# micro.net
KiCad netlist of a schematic drawn in Altium Designer
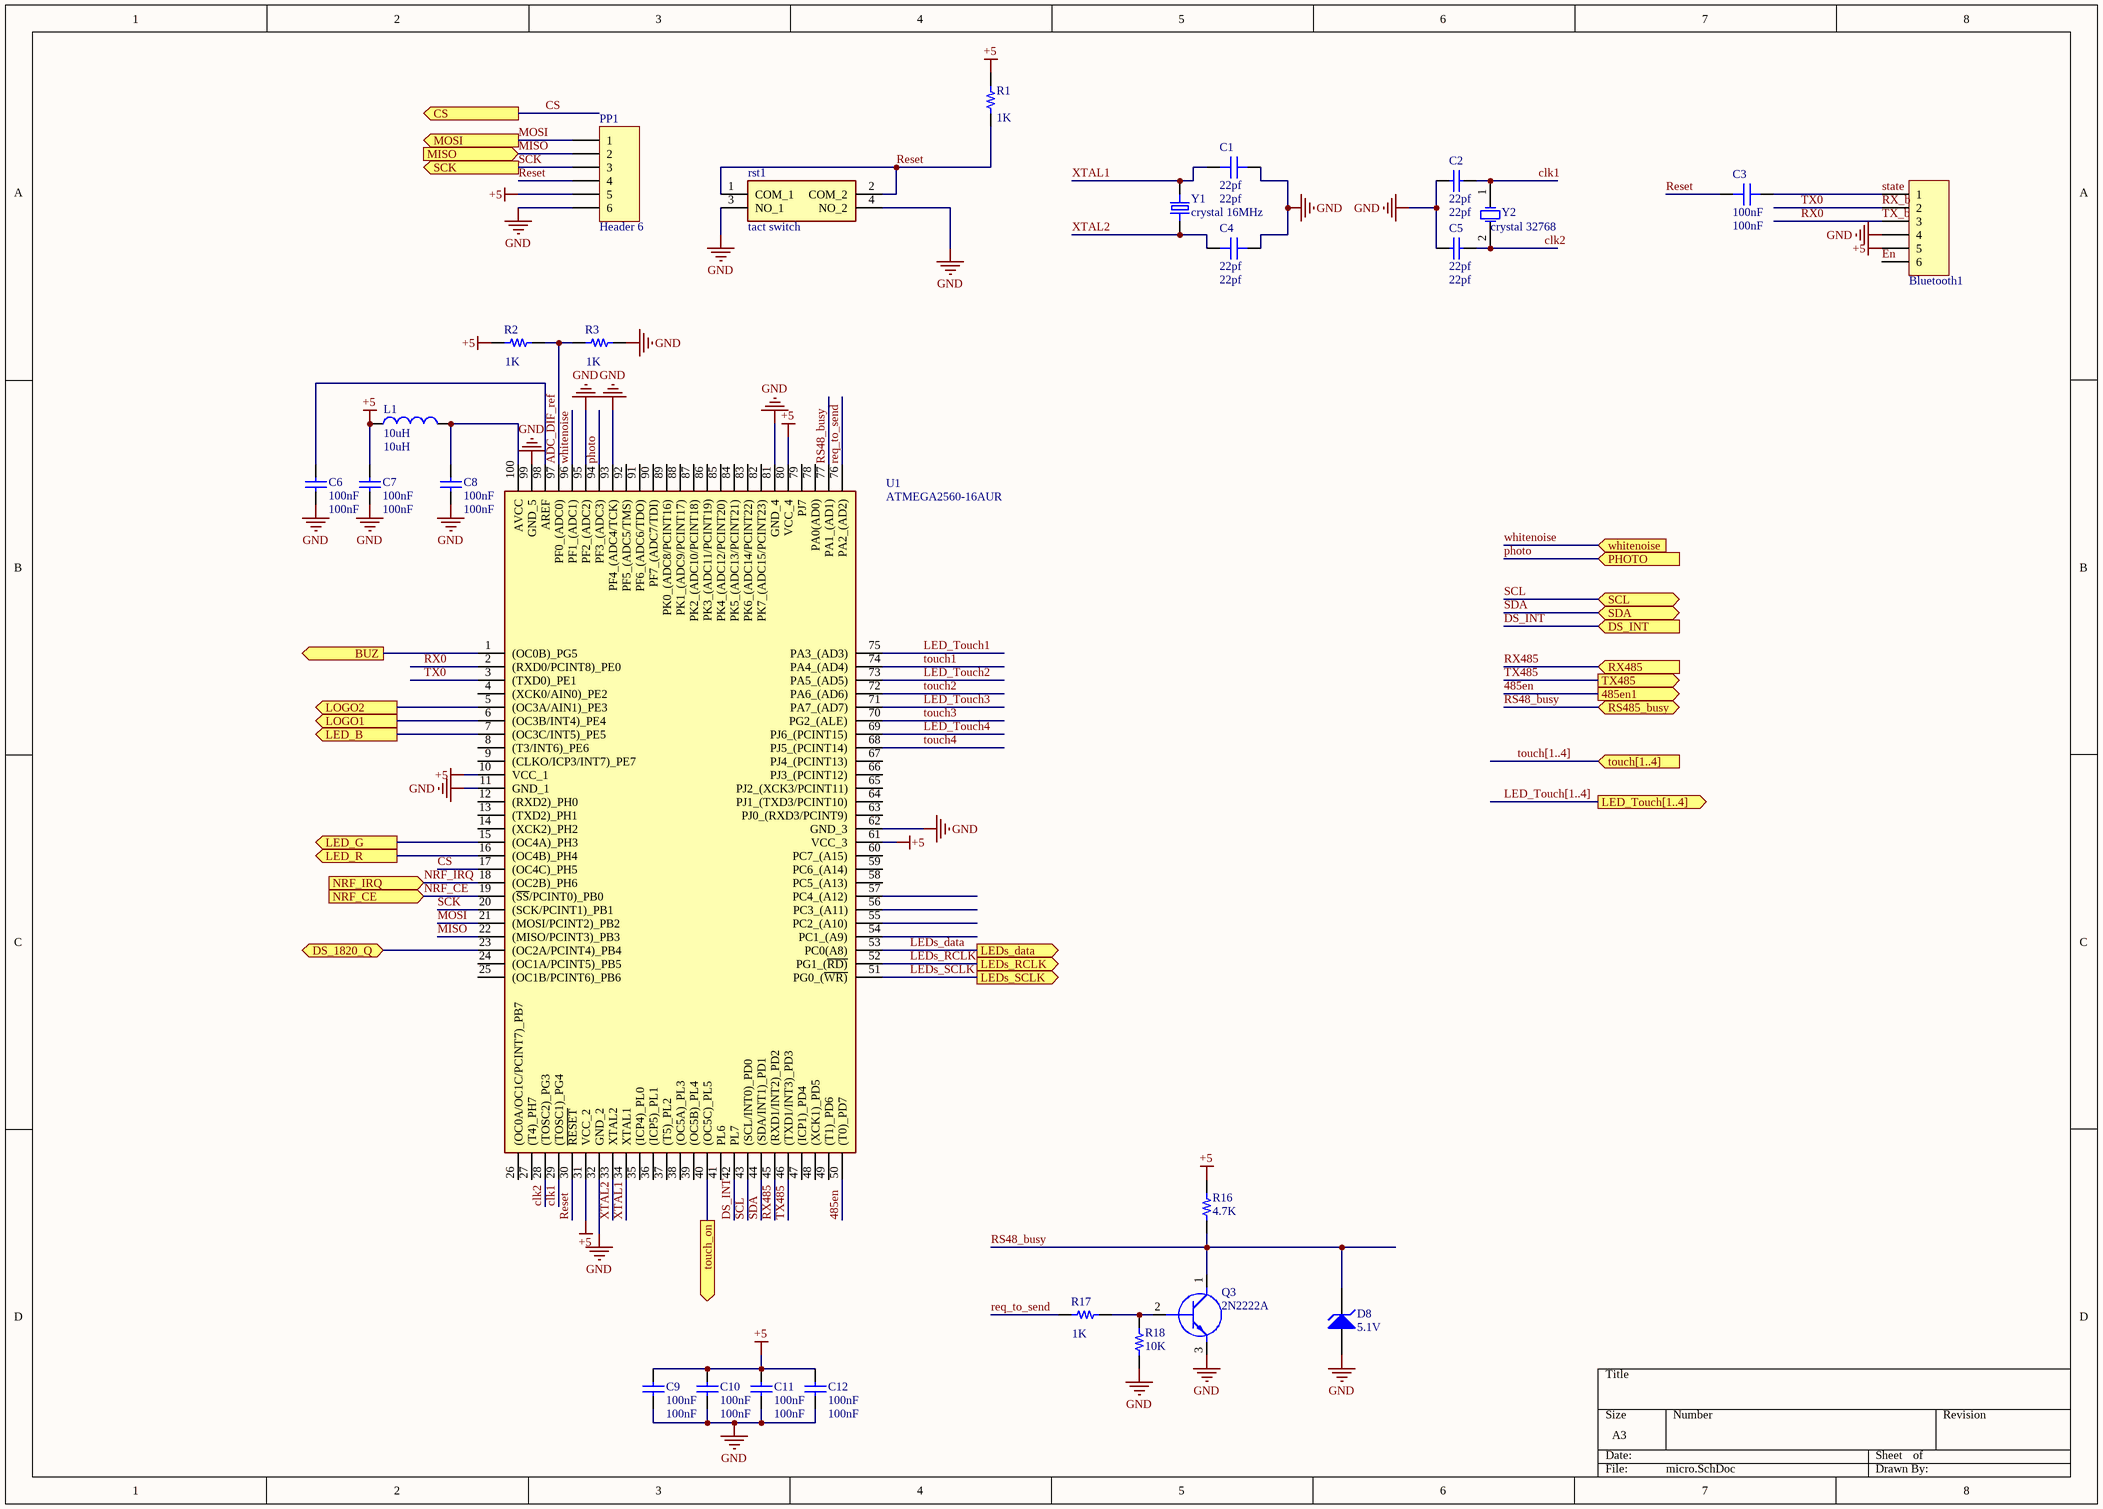
[diagram p0: micro.SchDoc]

(export (version "E")
  (design (tool "Eeschema 10.0.6"))
  (components
    (comp (ref "Bluetooth1")
      (value "Header 6")
      (footprint "H-1x6")
      (description "Header, 6-Pin , female")
      (libsource (lib "Mine-Discreet") (part "H-1x6"))
    )
    (comp (ref "C1")
      (value "22pf")
      (footprint "0603C")
      (description "CAP SMD 0603")
      (fields (field (name "PART NUMBER") "C0805X106K9RAC7800") (field (name "ALTIUM_VALUE") "22pf"))
      (libsource (lib "lamp control-ver2") (part "Capacitor"))
    )
    (comp (ref "C2")
      (value "22pf")
      (footprint "0603C")
      (description "CAP SMD 0603")
      (fields (field (name "ALTIUM_VALUE") "22pf") (field (name "PUBLISHER") "Altium Limited"))
      (libsource (lib "Miscellaneous Devices") (part "Cap"))
    )
    (comp (ref "C3")
      (value "100nF")
      (footprint "0603C")
      (description "CAP SMD 0603")
      (fields (field (name "PART NUMBER") "C0805X106K9RAC7800") (field (name "ALTIUM_VALUE") "100nF"))
      (libsource (lib "lamp control-ver2") (part "Capacitor"))
    )
    (comp (ref "C4")
      (value "22pf")
      (footprint "0603C")
      (description "CAP SMD 0603")
      (fields (field (name "PART NUMBER") "C0805X106K9RAC7800") (field (name "ALTIUM_VALUE") "22pf"))
      (libsource (lib "lamp control-ver2") (part "Capacitor"))
    )
    (comp (ref "C5")
      (value "22pf")
      (footprint "0603C")
      (description "CAP SMD 0603")
      (fields (field (name "ALTIUM_VALUE") "22pf") (field (name "PUBLISHER") "Altium Limited"))
      (libsource (lib "Miscellaneous Devices") (part "Cap"))
    )
    (comp (ref "C6")
      (value "100nF")
      (footprint "0603C")
      (description "CAP SMD 0603")
      (fields (field (name "ALTIUM_VALUE") "100nF") (field (name "PUBLISHER") "Altium Limited"))
      (libsource (lib "Miscellaneous Devices") (part "Cap"))
    )
    (comp (ref "C7")
      (value "100nF")
      (footprint "0603C")
      (description "CAP SMD 0603")
      (fields (field (name "ALTIUM_VALUE") "100nF") (field (name "PUBLISHER") "Altium Limited"))
      (libsource (lib "Miscellaneous Devices") (part "Cap"))
    )
    (comp (ref "C8")
      (value "100nF")
      (footprint "0603C")
      (description "CAP SMD 0603")
      (fields (field (name "ALTIUM_VALUE") "100nF") (field (name "PUBLISHER") "Altium Limited"))
      (libsource (lib "Miscellaneous Devices") (part "Cap"))
    )
    (comp (ref "C9")
      (value "100nF")
      (footprint "0603C")
      (description "CAP SMD 0603")
      (fields (field (name "ALTIUM_VALUE") "100nF") (field (name "PUBLISHER") "Altium Limited"))
      (libsource (lib "Miscellaneous Devices") (part "Cap"))
    )
    (comp (ref "C10")
      (value "100nF")
      (footprint "0603C")
      (description "CAP SMD 0603")
      (fields (field (name "ALTIUM_VALUE") "100nF") (field (name "PUBLISHER") "Altium Limited"))
      (libsource (lib "Miscellaneous Devices") (part "Cap"))
    )
    (comp (ref "C11")
      (value "100nF")
      (footprint "0603C")
      (description "CAP SMD 0603")
      (fields (field (name "ALTIUM_VALUE") "100nF") (field (name "PUBLISHER") "Altium Limited"))
      (libsource (lib "Miscellaneous Devices") (part "Cap"))
    )
    (comp (ref "C12")
      (value "100nF")
      (footprint "0603C")
      (description "CAP SMD 0603")
      (fields (field (name "ALTIUM_VALUE") "100nF") (field (name "PUBLISHER") "Altium Limited"))
      (libsource (lib "Miscellaneous Devices") (part "Cap"))
    )
    (comp (ref "D8")
      (value "5.1V")
      (footprint "Diode 1n4148 SMD")
      (description "Zener Diode 5.1v")
      (fields (field (name "PUBLISHER") "Altium Limited"))
      (libsource (lib "Miscellaneous Devices") (part "D Zener"))
    )
    (comp (ref "L1")
      (value "10uH")
      (footprint "IND1206")
      (description "Inductor 1206")
      (fields (field (name "ALTIUM_VALUE") "10uH") (field (name "PUBLISHER") "Altium Limited"))
      (libsource (lib "Miscellaneous Devices") (part "Inductor"))
    )
    (comp (ref "PP1")
      (value "Header 6")
      (footprint "HDR1X6")
      (description "Header, 6-Pin , female")
      (fields (field (name "PUBLISHER") "Altium Limited"))
      (libsource (lib "Miscellaneous Connectors") (part "Header 6"))
    )
    (comp (ref "Q3")
      (value "2N2222A")
      (footprint "soT95p280x130-3n")
      (description "Transistor BJT NPN SMD")
      (libsource (lib "*") (part "2N2222A"))
    )
    (comp (ref "R1")
      (value "1K")
      (footprint "0603R")
      (description "RES SMD 0603")
      (fields (field (name "PART NUMBER") "RCS0805100KFKEA"))
      (libsource (lib "lamp control-ver2") (part "Resistor"))
    )
    (comp (ref "R2")
      (value "1K")
      (footprint "0603R")
      (description "RES SMD 0603")
      (fields (field (name "PART NUMBER") "RCS0805100KFKEA"))
      (libsource (lib "lamp control-ver2") (part "Resistor"))
    )
    (comp (ref "R3")
      (value "1K")
      (footprint "0603R")
      (description "RES SMD 0603")
      (fields (field (name "PART NUMBER") "RCS0805100KFKEA"))
      (libsource (lib "lamp control-ver2") (part "Resistor"))
    )
    (comp (ref "R16")
      (value "4.7K")
      (footprint "0603R")
      (description "RES SMD 0603")
      (fields (field (name "PART NUMBER") "RCS0805100KFKEA"))
      (libsource (lib "lamp control-ver2") (part "Resistor"))
    )
    (comp (ref "R17")
      (value "1K")
      (footprint "0603R")
      (description "RES SMD 0603")
      (fields (field (name "PART NUMBER") "RCS0805100KFKEA"))
      (libsource (lib "lamp control-ver2") (part "Resistor"))
    )
    (comp (ref "R18")
      (value "10K")
      (footprint "0603R")
      (description "RES SMD 0603")
      (fields (field (name "PART NUMBER") "RCS0805100KFKEA"))
      (libsource (lib "lamp control-ver2") (part "Resistor"))
    )
    (comp (ref "rst1")
      (value "tact switch")
      (footprint "DTSM63NVB")
      (description "Push Button SMD - 4PIN")
      (fields
        (field (name "MANUFACTURER_PART_NUMBER") "DTSM-66R-V-T/R")
        (field (name "MOUSER PART NUMBER") "113-DTSM66RVTR")
      )
      (libsource (lib "*") (part "DTSM-66R-V-T_R"))
    )
    (comp (ref "U1")
      (value "ATMEGA2560-16AUR")
      (footprint "QFP50P1600X1600X120-100N")
      (description "ATMEGA2560-LQFP100")
      (fields (field (name "MOUSER PART NUMBER") "556-ATMEGA2560-16AUR"))
      (libsource (lib "*") (part "ATMEGA2560-16AUR"))
    )
    (comp (ref "Y1")
      (value "crystal 16MHz")
      (footprint "XTAL_ECS-180-S-5P-DN-TR")
      (description "Crystals 16MHz")
      (fields (field (name "MP") "ECS-180-S-5P-DN-TR") (field (name "MF") "ECS International"))
      (libsource (lib "CrystalSMD") (part "ECS-180-S-5P-DN-TR"))
    )
    (comp (ref "Y2")
      (value "crystal 32768")
      (footprint "XTAL RTC")
      (description "RTC crystal")
      (libsource (lib "My Library") (part "XTAL"))
    )
  )
  (nets
    (net (code "1") (name "+5") (class "Default")
      (node (ref "Bluetooth1") (pin "5") (pinfunction "5_5") (pintype "passive"))
      (node (ref "C10") (pin "1") (pinfunction "1_1") (pintype "passive"))
      (node (ref "C11") (pin "1") (pinfunction "1_1") (pintype "passive"))
      (node (ref "C12") (pin "1") (pinfunction "1_1") (pintype "passive"))
      (node (ref "C7") (pin "1") (pinfunction "1_1") (pintype "passive"))
      (node (ref "C9") (pin "1") (pinfunction "1_1") (pintype "passive"))
      (node (ref "L1") (pin "1") (pinfunction "1_1") (pintype "passive"))
      (node (ref "PP1") (pin "5") (pinfunction "5_5") (pintype "passive"))
      (node (ref "R1") (pin "2") (pinfunction "2_2") (pintype "passive"))
      (node (ref "R16") (pin "1") (pinfunction "1_1") (pintype "passive"))
      (node (ref "R2") (pin "2") (pinfunction "2_2") (pintype "passive"))
      (node (ref "U1") (pin "10") (pinfunction "VCC_1_10") (pintype "passive"))
      (node (ref "U1") (pin "31") (pinfunction "VCC_2_31") (pintype "passive"))
      (node (ref "U1") (pin "61") (pinfunction "VCC_3_61") (pintype "passive"))
      (node (ref "U1") (pin "80") (pinfunction "VCC_4_80") (pintype "passive"))
    )
    (net (code "2") (name "/485en") (class "Default")
      (node (ref "U1") (pin "50") (pinfunction "(T0)_PD7_50") (pintype "passive"))
    )
    (net (code "3") (name "/ADC_DIF_ref") (class "Default")
      (node (ref "R2") (pin "1") (pinfunction "1_1") (pintype "passive"))
      (node (ref "R3") (pin "2") (pinfunction "2_2") (pintype "passive"))
      (node (ref "U1") (pin "97") (pinfunction "PF0_(ADC0)_97") (pintype "passive"))
    )
    (net (code "4") (name "/BUZ") (class "Default")
      (node (ref "U1") (pin "1") (pinfunction "(OC0B)_PG5_1") (pintype "passive"))
    )
    (net (code "5") (name "/CS") (class "Default")
      (node (ref "U1") (pin "17") (pinfunction "(OC4C)_PH5_17") (pintype "passive"))
    )
    (net (code "6") (name "/DS_1820_Q") (class "Default")
      (node (ref "U1") (pin "23") (pinfunction "(OC2A/PCINT4)_PB4_23") (pintype "passive"))
    )
    (net (code "7") (name "/DS_INT") (class "Default")
      (node (ref "U1") (pin "42") (pinfunction "PL7_42") (pintype "passive"))
    )
    (net (code "8") (name "/En") (class "Default")
      (node (ref "Bluetooth1") (pin "6") (pinfunction "6_6") (pintype "passive"))
    )
    (net (code "9") (name "/LED_B") (class "Default")
      (node (ref "U1") (pin "7") (pinfunction "(OC3C/INT5)_PE5_7") (pintype "passive"))
    )
    (net (code "10") (name "/LED_G") (class "Default")
      (node (ref "U1") (pin "15") (pinfunction "(OC4A)_PH3_15") (pintype "passive"))
    )
    (net (code "11") (name "/LED_R") (class "Default")
      (node (ref "U1") (pin "16") (pinfunction "(OC4B)_PH4_16") (pintype "passive"))
    )
    (net (code "12") (name "/LED_Touch1") (class "Default")
      (node (ref "U1") (pin "75") (pinfunction "PA3_(AD3)_75") (pintype "passive"))
    )
    (net (code "13") (name "/LED_Touch2") (class "Default")
      (node (ref "U1") (pin "73") (pinfunction "PA5_(AD5)_73") (pintype "passive"))
    )
    (net (code "14") (name "/LED_Touch3") (class "Default")
      (node (ref "U1") (pin "71") (pinfunction "PA7_(AD7)_71") (pintype "passive"))
    )
    (net (code "15") (name "/LED_Touch4") (class "Default")
      (node (ref "U1") (pin "69") (pinfunction "PJ6_(PCINT15)_69") (pintype "passive"))
    )
    (net (code "17") (name "/LEDs_RCLK") (class "Default")
      (node (ref "U1") (pin "52") (pinfunction "PG1_(~{RD)}_52") (pintype "passive"))
    )
    (net (code "18") (name "/LEDs_SCLK") (class "Default")
      (node (ref "U1") (pin "51") (pinfunction "PG0_(~{WR)}_51") (pintype "passive"))
    )
    (net (code "19") (name "/LEDs_data") (class "Default")
      (node (ref "U1") (pin "53") (pinfunction "PC0(A8)_53") (pintype "passive"))
    )
    (net (code "20") (name "/LOGO1") (class "Default")
      (node (ref "U1") (pin "6") (pinfunction "(OC3B/INT4)_PE4_6") (pintype "passive"))
    )
    (net (code "21") (name "/LOGO2") (class "Default")
      (node (ref "U1") (pin "5") (pinfunction "(OC3A/AIN1)_PE3_5") (pintype "passive"))
    )
    (net (code "22") (name "/MISO") (class "Default")
      (node (ref "PP1") (pin "2") (pinfunction "2_2") (pintype "passive"))
      (node (ref "U1") (pin "22") (pinfunction "(MISO/PCINT3)_PB3_22") (pintype "passive"))
    )
    (net (code "23") (name "/MOSI") (class "Default")
      (node (ref "PP1") (pin "1") (pinfunction "1_1") (pintype "passive"))
      (node (ref "U1") (pin "21") (pinfunction "(MOSI/PCINT2)_PB2_21") (pintype "passive"))
    )
    (net (code "24") (name "/NRF_CE") (class "Default")
      (node (ref "U1") (pin "19") (pinfunction "(~{SS}/PCINT0)_PB0_19") (pintype "passive"))
    )
    (net (code "25") (name "/NRF_IRQ") (class "Default")
      (node (ref "U1") (pin "18") (pinfunction "(OC2B)_PH6_18") (pintype "passive"))
    )
    (net (code "26") (name "/RS48_busy") (class "Default")
      (node (ref "D8") (pin "2") (pinfunction "K_2") (pintype "passive"))
      (node (ref "Q3") (pin "1") (pinfunction "C_1") (pintype "passive"))
      (node (ref "R16") (pin "2") (pinfunction "2_2") (pintype "passive"))
      (node (ref "U1") (pin "77") (pinfunction "PA1_(AD1)_77") (pintype "passive"))
    )
    (net (code "27") (name "/RX0") (class "Default")
      (node (ref "Bluetooth1") (pin "3") (pinfunction "3_3") (pintype "passive"))
      (node (ref "U1") (pin "2") (pinfunction "(RXD0/PCINT8)_PE0_2") (pintype "passive"))
    )
    (net (code "28") (name "/RX485") (class "Default")
      (node (ref "U1") (pin "45") (pinfunction "(RXD1/INT2)_PD2_45") (pintype "passive"))
    )
    (net (code "29") (name "/RX_b") (class "Default")
      (node (ref "Bluetooth1") (pin "2") (pinfunction "2_2") (pintype "passive"))
      (node (ref "U1") (pin "3") (pinfunction "(TXD0)_PE1_3") (pintype "passive"))
    )
    (net (code "30") (name "/Reset") (class "Default")
      (node (ref "C3") (pin "2") (pinfunction "2_2") (pintype "passive"))
      (node (ref "PP1") (pin "4") (pinfunction "4_4") (pintype "passive"))
      (node (ref "R1") (pin "1") (pinfunction "1_1") (pintype "passive"))
      (node (ref "U1") (pin "30") (pinfunction "~{RESET}_30") (pintype "passive"))
      (node (ref "rst1") (pin "1") (pinfunction "COM_1_1") (pintype "passive"))
      (node (ref "rst1") (pin "2") (pinfunction "COM_2_2") (pintype "passive"))
    )
    (net (code "31") (name "/SCK") (class "Default")
      (node (ref "PP1") (pin "3") (pinfunction "3_3") (pintype "passive"))
      (node (ref "U1") (pin "20") (pinfunction "(SCK/PCINT1)_PB1_20") (pintype "passive"))
    )
    (net (code "32") (name "/SCL") (class "Default")
      (node (ref "U1") (pin "43") (pinfunction "(SCL/INT0)_PD0_43") (pintype "passive"))
    )
    (net (code "33") (name "/SDA") (class "Default")
      (node (ref "U1") (pin "44") (pinfunction "(SDA/INT1)_PD1_44") (pintype "passive"))
    )
    (net (code "34") (name "/TX485") (class "Default")
      (node (ref "U1") (pin "46") (pinfunction "(TXD1/INT3)_PD3_46") (pintype "passive"))
    )
    (net (code "35") (name "/XTAL1") (class "Default")
      (node (ref "C1") (pin "2") (pinfunction "2_2") (pintype "passive"))
      (node (ref "U1") (pin "34") (pinfunction "XTAL1_34") (pintype "passive"))
      (node (ref "Y1") (pin "2") (pinfunction "2_2") (pintype "passive"))
    )
    (net (code "36") (name "/XTAL2") (class "Default")
      (node (ref "C4") (pin "2") (pinfunction "2_2") (pintype "passive"))
      (node (ref "U1") (pin "33") (pinfunction "XTAL2_33") (pintype "passive"))
      (node (ref "Y1") (pin "1") (pinfunction "1_1") (pintype "passive"))
    )
    (net (code "37") (name "/clk1") (class "Default")
      (node (ref "C2") (pin "2") (pinfunction "2_2") (pintype "passive"))
      (node (ref "U1") (pin "29") (pinfunction "(TOSC1)_PG4_29") (pintype "passive"))
      (node (ref "Y2") (pin "1") (pinfunction "OSC1_1") (pintype "passive"))
    )
    (net (code "38") (name "/clk2") (class "Default")
      (node (ref "C5") (pin "1") (pinfunction "1_1") (pintype "passive"))
      (node (ref "U1") (pin "28") (pinfunction "(TOSC2)_PG3_28") (pintype "passive"))
      (node (ref "Y2") (pin "2") (pinfunction "OSC2_2") (pintype "passive"))
    )
    (net (code "39") (name "/photo") (class "Default")
      (node (ref "U1") (pin "94") (pinfunction "PF3_(ADC3)_94") (pintype "passive"))
    )
    (net (code "40") (name "/req_to_send") (class "Default")
      (node (ref "R17") (pin "2") (pinfunction "2_2") (pintype "passive"))
      (node (ref "U1") (pin "76") (pinfunction "PA2_(AD2)_76") (pintype "passive"))
    )
    (net (code "41") (name "/state") (class "Default")
      (node (ref "Bluetooth1") (pin "1") (pinfunction "1_1") (pintype "passive"))
      (node (ref "C3") (pin "1") (pinfunction "1_1") (pintype "passive"))
    )
    (net (code "42") (name "/touch1") (class "Default")
      (node (ref "U1") (pin "74") (pinfunction "PA4_(AD4)_74") (pintype "passive"))
    )
    (net (code "43") (name "/touch2") (class "Default")
      (node (ref "U1") (pin "72") (pinfunction "PA6_(AD6)_72") (pintype "passive"))
    )
    (net (code "44") (name "/touch3") (class "Default")
      (node (ref "U1") (pin "70") (pinfunction "PG2_(ALE)_70") (pintype "passive"))
    )
    (net (code "45") (name "/touch4") (class "Default")
      (node (ref "U1") (pin "68") (pinfunction "PJ5_(PCINT14)_68") (pintype "passive"))
    )
    (net (code "47") (name "/touch_on") (class "Default")
      (node (ref "U1") (pin "40") (pinfunction "(OC5C)_PL5_40") (pintype "passive"))
    )
    (net (code "48") (name "/whitenoise") (class "Default")
      (node (ref "U1") (pin "96") (pinfunction "PF1_(ADC1)_96") (pintype "passive"))
    )
    (net (code "49") (name "GND") (class "Default")
      (node (ref "Bluetooth1") (pin "4") (pinfunction "4_4") (pintype "passive"))
      (node (ref "C1") (pin "1") (pinfunction "1_1") (pintype "passive"))
      (node (ref "C10") (pin "2") (pinfunction "2_2") (pintype "passive"))
      (node (ref "C11") (pin "2") (pinfunction "2_2") (pintype "passive"))
      (node (ref "C12") (pin "2") (pinfunction "2_2") (pintype "passive"))
      (node (ref "C2") (pin "1") (pinfunction "1_1") (pintype "passive"))
      (node (ref "C4") (pin "1") (pinfunction "1_1") (pintype "passive"))
      (node (ref "C5") (pin "2") (pinfunction "2_2") (pintype "passive"))
      (node (ref "C6") (pin "2") (pinfunction "2_2") (pintype "passive"))
      (node (ref "C7") (pin "2") (pinfunction "2_2") (pintype "passive"))
      (node (ref "C8") (pin "2") (pinfunction "2_2") (pintype "passive"))
      (node (ref "C9") (pin "2") (pinfunction "2_2") (pintype "passive"))
      (node (ref "D8") (pin "1") (pinfunction "A_1") (pintype "passive"))
      (node (ref "PP1") (pin "6") (pinfunction "6_6") (pintype "passive"))
      (node (ref "Q3") (pin "3") (pinfunction "E_3") (pintype "passive"))
      (node (ref "R18") (pin "2") (pinfunction "2_2") (pintype "passive"))
      (node (ref "R3") (pin "1") (pinfunction "1_1") (pintype "passive"))
      (node (ref "U1") (pin "11") (pinfunction "GND_1_11") (pintype "passive"))
      (node (ref "U1") (pin "32") (pinfunction "GND_2_32") (pintype "passive"))
      (node (ref "U1") (pin "62") (pinfunction "GND_3_62") (pintype "passive"))
      (node (ref "U1") (pin "81") (pinfunction "GND_4_81") (pintype "passive"))
      (node (ref "U1") (pin "93") (pinfunction "PF4_(ADC4/TCK)_93") (pintype "passive"))
      (node (ref "U1") (pin "95") (pinfunction "PF2_(ADC2)_95") (pintype "passive"))
      (node (ref "U1") (pin "99") (pinfunction "GND_5_99") (pintype "passive"))
      (node (ref "rst1") (pin "3") (pinfunction "NO_1_3") (pintype "passive"))
      (node (ref "rst1") (pin "4") (pinfunction "NO_2_4") (pintype "passive"))
    )
    (net (code "50") (name "Net-(Q3-B)") (class "Default")
      (node (ref "Q3") (pin "2") (pinfunction "B_2") (pintype "passive"))
      (node (ref "R17") (pin "1") (pinfunction "1_1") (pintype "passive"))
      (node (ref "R18") (pin "1") (pinfunction "1_1") (pintype "passive"))
    )
    (net (code "51") (name "Net-(U1-AREF)") (class "Default")
      (node (ref "C6") (pin "1") (pinfunction "1_1") (pintype "passive"))
      (node (ref "U1") (pin "98") (pinfunction "AREF_98") (pintype "passive"))
    )
    (net (code "52") (name "Net-(U1-AVCC)") (class "Default")
      (node (ref "C8") (pin "1") (pinfunction "1_1") (pintype "passive"))
      (node (ref "L1") (pin "2") (pinfunction "2_2") (pintype "passive"))
      (node (ref "U1") (pin "100") (pinfunction "AVCC_100") (pintype "passive"))
    )
    (net (code "53") (name "unconnected-(U1-(CLKO{slash}ICP3{slash}INT7)_PE7-Pad9)") (class "Default")
      (node (ref "U1") (pin "9") (pinfunction "(CLKO/ICP3/INT7)_PE7_9") (pintype "passive"))
    )
    (net (code "54") (name "unconnected-(U1-(ICP1)_PD4-Pad47)") (class "Default")
      (node (ref "U1") (pin "47") (pinfunction "(ICP1)_PD4_47") (pintype "passive"))
    )
    (net (code "55") (name "unconnected-(U1-(ICP4)_PL0-Pad35)") (class "Default")
      (node (ref "U1") (pin "35") (pinfunction "(ICP4)_PL0_35") (pintype "passive"))
    )
    (net (code "56") (name "unconnected-(U1-(ICP5)_PL1-Pad36)") (class "Default")
      (node (ref "U1") (pin "36") (pinfunction "(ICP5)_PL1_36") (pintype "passive"))
    )
    (net (code "57") (name "unconnected-(U1-(OC0A{slash}OC1C{slash}PCINT7)_PB7-Pad26)") (class "Default")
      (node (ref "U1") (pin "26") (pinfunction "(OC0A/OC1C/PCINT7)_PB7_26") (pintype "passive"))
    )
    (net (code "58") (name "unconnected-(U1-(OC1A{slash}PCINT5)_PB5-Pad24)") (class "Default")
      (node (ref "U1") (pin "24") (pinfunction "(OC1A/PCINT5)_PB5_24") (pintype "passive"))
    )
    (net (code "59") (name "unconnected-(U1-(OC1B{slash}PCINT6)_PB6-Pad25)") (class "Default")
      (node (ref "U1") (pin "25") (pinfunction "(OC1B/PCINT6)_PB6_25") (pintype "passive"))
    )
    (net (code "60") (name "unconnected-(U1-(OC5A)_PL3-Pad38)") (class "Default")
      (node (ref "U1") (pin "38") (pinfunction "(OC5A)_PL3_38") (pintype "passive"))
    )
    (net (code "61") (name "unconnected-(U1-(OC5B)_PL4-Pad39)") (class "Default")
      (node (ref "U1") (pin "39") (pinfunction "(OC5B)_PL4_39") (pintype "passive"))
    )
    (net (code "62") (name "unconnected-(U1-(RXD2)_PH0-Pad12)") (class "Default")
      (node (ref "U1") (pin "12") (pinfunction "(RXD2)_PH0_12") (pintype "passive"))
    )
    (net (code "63") (name "unconnected-(U1-(T1)_PD6-Pad49)") (class "Default")
      (node (ref "U1") (pin "49") (pinfunction "(T1)_PD6_49") (pintype "passive"))
    )
    (net (code "64") (name "unconnected-(U1-(T3{slash}INT6)_PE6-Pad8)") (class "Default")
      (node (ref "U1") (pin "8") (pinfunction "(T3/INT6)_PE6_8") (pintype "passive"))
    )
    (net (code "65") (name "unconnected-(U1-(T4)_PH7-Pad27)") (class "Default")
      (node (ref "U1") (pin "27") (pinfunction "(T4)_PH7_27") (pintype "passive"))
    )
    (net (code "66") (name "unconnected-(U1-(T5)_PL2-Pad37)") (class "Default")
      (node (ref "U1") (pin "37") (pinfunction "(T5)_PL2_37") (pintype "passive"))
    )
    (net (code "67") (name "unconnected-(U1-(TXD2)_PH1-Pad13)") (class "Default")
      (node (ref "U1") (pin "13") (pinfunction "(TXD2)_PH1_13") (pintype "passive"))
    )
    (net (code "68") (name "unconnected-(U1-(XCK0{slash}AIN0)_PE2-Pad4)") (class "Default")
      (node (ref "U1") (pin "4") (pinfunction "(XCK0/AIN0)_PE2_4") (pintype "passive"))
    )
    (net (code "69") (name "unconnected-(U1-(XCK1)_PD5-Pad48)") (class "Default")
      (node (ref "U1") (pin "48") (pinfunction "(XCK1)_PD5_48") (pintype "passive"))
    )
    (net (code "70") (name "unconnected-(U1-(XCK2)_PH2-Pad14)") (class "Default")
      (node (ref "U1") (pin "14") (pinfunction "(XCK2)_PH2_14") (pintype "passive"))
    )
    (net (code "71") (name "unconnected-(U1-PA0(AD0)-Pad78)") (class "Default")
      (node (ref "U1") (pin "78") (pinfunction "PA0(AD0)_78") (pintype "passive"))
    )
    (net (code "72") (name "unconnected-(U1-PC1_(A9)-Pad54)") (class "Default")
      (node (ref "U1") (pin "54") (pinfunction "PC1_(A9)_54") (pintype "passive"))
    )
    (net (code "73") (name "unconnected-(U1-PC2_(A10)-Pad55)") (class "Default")
      (node (ref "U1") (pin "55") (pinfunction "PC2_(A10)_55") (pintype "passive"))
    )
    (net (code "74") (name "unconnected-(U1-PC3_(A11)-Pad56)") (class "Default")
      (node (ref "U1") (pin "56") (pinfunction "PC3_(A11)_56") (pintype "passive"))
    )
    (net (code "75") (name "unconnected-(U1-PC4_(A12)-Pad57)") (class "Default")
      (node (ref "U1") (pin "57") (pinfunction "PC4_(A12)_57") (pintype "passive"))
    )
    (net (code "76") (name "unconnected-(U1-PC5_(A13)-Pad58)") (class "Default")
      (node (ref "U1") (pin "58") (pinfunction "PC5_(A13)_58") (pintype "passive"))
    )
    (net (code "77") (name "unconnected-(U1-PC6_(A14)-Pad59)") (class "Default")
      (node (ref "U1") (pin "59") (pinfunction "PC6_(A14)_59") (pintype "passive"))
    )
    (net (code "78") (name "unconnected-(U1-PC7_(A15)-Pad60)") (class "Default")
      (node (ref "U1") (pin "60") (pinfunction "PC7_(A15)_60") (pintype "passive"))
    )
    (net (code "79") (name "unconnected-(U1-PF5_(ADC5{slash}TMS)-Pad92)") (class "Default")
      (node (ref "U1") (pin "92") (pinfunction "PF5_(ADC5/TMS)_92") (pintype "passive"))
    )
    (net (code "80") (name "unconnected-(U1-PF6_(ADC6{slash}TDO)-Pad91)") (class "Default")
      (node (ref "U1") (pin "91") (pinfunction "PF6_(ADC6/TDO)_91") (pintype "passive"))
    )
    (net (code "81") (name "unconnected-(U1-PF7_(ADC7{slash}TDI)-Pad90)") (class "Default")
      (node (ref "U1") (pin "90") (pinfunction "PF7_(ADC7/TDI)_90") (pintype "passive"))
    )
    (net (code "82") (name "unconnected-(U1-PJ0_(RXD3{slash}PCINT9)-Pad63)") (class "Default")
      (node (ref "U1") (pin "63") (pinfunction "PJ0_(RXD3/PCINT9)_63") (pintype "passive"))
    )
    (net (code "83") (name "unconnected-(U1-PJ1_(TXD3{slash}PCINT10)-Pad64)") (class "Default")
      (node (ref "U1") (pin "64") (pinfunction "PJ1_(TXD3/PCINT10)_64") (pintype "passive"))
    )
    (net (code "84") (name "unconnected-(U1-PJ2_(XCK3{slash}PCINT11)-Pad65)") (class "Default")
      (node (ref "U1") (pin "65") (pinfunction "PJ2_(XCK3/PCINT11)_65") (pintype "passive"))
    )
    (net (code "85") (name "unconnected-(U1-PJ3_(PCINT12)-Pad66)") (class "Default")
      (node (ref "U1") (pin "66") (pinfunction "PJ3_(PCINT12)_66") (pintype "passive"))
    )
    (net (code "86") (name "unconnected-(U1-PJ4_(PCINT13)-Pad67)") (class "Default")
      (node (ref "U1") (pin "67") (pinfunction "PJ4_(PCINT13)_67") (pintype "passive"))
    )
    (net (code "87") (name "unconnected-(U1-PJ7-Pad79)") (class "Default")
      (node (ref "U1") (pin "79") (pinfunction "PJ7_79") (pintype "passive"))
    )
    (net (code "88") (name "unconnected-(U1-PK0_(ADC8{slash}PCINT16)-Pad89)") (class "Default")
      (node (ref "U1") (pin "89") (pinfunction "PK0_(ADC8/PCINT16)_89") (pintype "passive"))
    )
    (net (code "89") (name "unconnected-(U1-PK1_(ADC9{slash}PCINT17)-Pad88)") (class "Default")
      (node (ref "U1") (pin "88") (pinfunction "PK1_(ADC9/PCINT17)_88") (pintype "passive"))
    )
    (net (code "90") (name "unconnected-(U1-PK2_(ADC10{slash}PCINT18)-Pad87)") (class "Default")
      (node (ref "U1") (pin "87") (pinfunction "PK2_(ADC10/PCINT18)_87") (pintype "passive"))
    )
    (net (code "91") (name "unconnected-(U1-PK3_(ADC11{slash}PCINT19)-Pad86)") (class "Default")
      (node (ref "U1") (pin "86") (pinfunction "PK3_(ADC11/PCINT19)_86") (pintype "passive"))
    )
    (net (code "92") (name "unconnected-(U1-PK4_(ADC12{slash}PCINT20)-Pad85)") (class "Default")
      (node (ref "U1") (pin "85") (pinfunction "PK4_(ADC12/PCINT20)_85") (pintype "passive"))
    )
    (net (code "93") (name "unconnected-(U1-PK5_(ADC13{slash}PCINT21)-Pad84)") (class "Default")
      (node (ref "U1") (pin "84") (pinfunction "PK5_(ADC13/PCINT21)_84") (pintype "passive"))
    )
    (net (code "94") (name "unconnected-(U1-PK6_(ADC14{slash}PCINT22)-Pad83)") (class "Default")
      (node (ref "U1") (pin "83") (pinfunction "PK6_(ADC14/PCINT22)_83") (pintype "passive"))
    )
    (net (code "95") (name "unconnected-(U1-PK7_(ADC15{slash}PCINT23)-Pad82)") (class "Default")
      (node (ref "U1") (pin "82") (pinfunction "PK7_(ADC15/PCINT23)_82") (pintype "passive"))
    )
    (net (code "96") (name "unconnected-(U1-PL6-Pad41)") (class "Default")
      (node (ref "U1") (pin "41") (pinfunction "PL6_41") (pintype "passive"))
    )
  )
)
